# ppm-converter.net
KiCad netlist of a schematic drawn in EAGLE
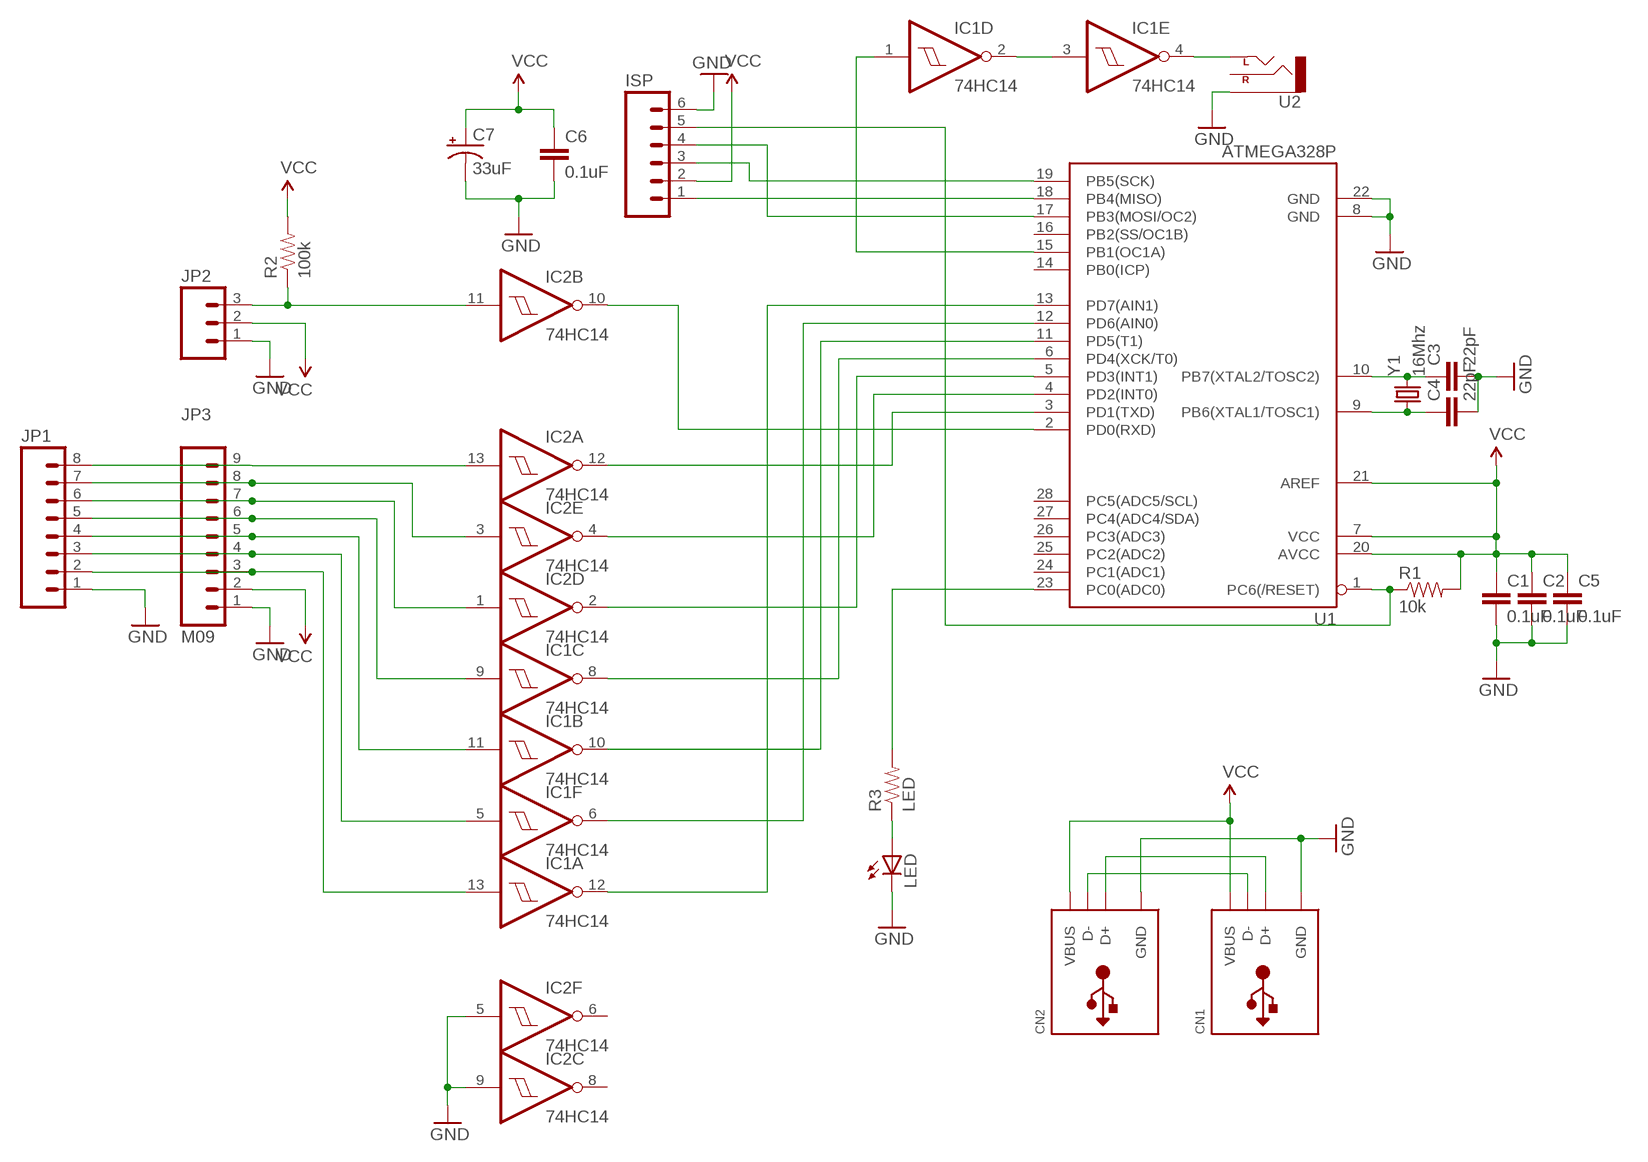
[diagram p0: schematic, sheet 1]

(export (version "E")
  (design (tool "Eeschema 10.0.6"))
  (components
    (comp (ref "C1")
      (value "0.1uF")
      (footprint "eagle-import:CAP-PTH-SMALL")
      (libsource (lib "eagle-import") (part "CAPPTH"))
    )
    (comp (ref "C2")
      (value "0.1uF")
      (footprint "eagle-import:CAP-PTH-SMALL")
      (libsource (lib "eagle-import") (part "CAPPTH"))
    )
    (comp (ref "C3")
      (value "22pF")
      (footprint "eagle-import:CAP-PTH-SMALL")
      (libsource (lib "eagle-import") (part "CAPPTH"))
    )
    (comp (ref "C4")
      (value "22pF")
      (footprint "eagle-import:CAP-PTH-SMALL")
      (libsource (lib "eagle-import") (part "CAPPTH"))
    )
    (comp (ref "C5")
      (value "0.1uF")
      (footprint "eagle-import:CAP-PTH-SMALL")
      (libsource (lib "eagle-import") (part "CAPPTH"))
    )
    (comp (ref "C6")
      (value "0.1uF")
      (footprint "eagle-import:CAP-PTH-SMALL")
      (libsource (lib "eagle-import") (part "CAPPTH"))
    )
    (comp (ref "C7")
      (value "33uF")
      (footprint "eagle-import:CPOL-RADIAL-100UF-25V")
      (libsource (lib "eagle-import") (part "CAP_POLPTH1"))
    )
    (comp (ref "CN1")
      (value "USB_TYPEAPTHFML")
      (footprint "eagle-import:USB_HOST-PTH")
      (libsource (lib "eagle-import") (part "USB_TYPEAPTHFML"))
    )
    (comp (ref "CN2")
      (value "USB_TYPEAPTHFML")
      (footprint "eagle-import:USB_HOST-PTH")
      (libsource (lib "eagle-import") (part "USB_TYPEAPTHFML"))
    )
    (comp (ref "IC1")
      (value "74HC14")
      (footprint "eagle-import:DIL14")
      (libsource (lib "eagle-import") (part "7414NHC"))
    )
    (comp (ref "IC2")
      (value "74HC14")
      (footprint "eagle-import:DIL14")
      (libsource (lib "eagle-import") (part "7414NHC"))
    )
    (comp (ref "ISP")
      (value "M06SIP")
      (footprint "eagle-import:1X06")
      (libsource (lib "eagle-import") (part "M06SIP"))
    )
    (comp (ref "JP1")
      (value "M081X08")
      (footprint "eagle-import:1X08")
      (libsource (lib "eagle-import") (part "M081X08"))
    )
    (comp (ref "JP2")
      (value "M03PTH")
      (footprint "eagle-import:1X03")
      (libsource (lib "eagle-import") (part "M03PTH"))
    )
    (comp (ref "JP3")
      (value "M09")
      (footprint "eagle-import:1X09")
      (libsource (lib "eagle-import") (part "M09"))
    )
    (comp (ref "LED")
      (value "LED5MM-KIT")
      (footprint "eagle-import:LED5MM-KIT")
      (libsource (lib "eagle-import") (part "LED5MM-KIT"))
    )
    (comp (ref "R1")
      (value "10k")
      (footprint "eagle-import:AXIAL-0.3")
      (libsource (lib "eagle-import") (part "RESISTORAXIAL-0.3"))
    )
    (comp (ref "R2")
      (value "100k")
      (footprint "eagle-import:AXIAL-0.3")
      (libsource (lib "eagle-import") (part "RESISTORAXIAL-0.3"))
    )
    (comp (ref "R3")
      (value "LED")
      (footprint "eagle-import:AXIAL-0.3")
      (libsource (lib "eagle-import") (part "RESISTORAXIAL-0.3"))
    )
    (comp (ref "U1")
      (value "ATMEGA328P")
      (footprint "eagle-import:DIL28-3")
      (libsource (lib "eagle-import") (part "ATMEGA328P_PDIP"))
    )
    (comp (ref "U2")
      (value "AUDIO-JACKPTH")
      (footprint "eagle-import:AUDIO-JACK")
      (libsource (lib "eagle-import") (part "AUDIO-JACKPTH"))
    )
    (comp (ref "Y1")
      (value "16Mhz")
      (footprint "eagle-import:HC49US")
      (libsource (lib "eagle-import") (part "CRYSTALHC49US"))
    )
  )
  (nets
    (net (code "1") (name "GND") (class "Default")
      (node (ref "C1") (pin "2") (pinfunction "2_2") (pintype "passive"))
      (node (ref "C2") (pin "2") (pinfunction "2_2") (pintype "passive"))
      (node (ref "C3") (pin "2") (pinfunction "2_2") (pintype "passive"))
      (node (ref "C4") (pin "2") (pinfunction "2_2") (pintype "passive"))
      (node (ref "C5") (pin "2") (pinfunction "2_2") (pintype "passive"))
      (node (ref "C6") (pin "2") (pinfunction "2_2") (pintype "passive"))
      (node (ref "C7") (pin "2") (pinfunction "-_2") (pintype "passive"))
      (node (ref "CN1") (pin "GND") (pinfunction "GND_GND") (pintype "power_in"))
      (node (ref "CN2") (pin "GND") (pinfunction "GND_GND") (pintype "power_in"))
      (node (ref "IC2") (pin "5") (pinfunction "I_5") (pintype "input"))
      (node (ref "IC2") (pin "9") (pinfunction "I_9") (pintype "input"))
      (node (ref "ISP") (pin "6") (pinfunction "6_6") (pintype "passive"))
      (node (ref "JP1") (pin "1") (pinfunction "1_1") (pintype "passive"))
      (node (ref "JP2") (pin "1") (pinfunction "1_1") (pintype "passive"))
      (node (ref "JP3") (pin "1") (pinfunction "1_1") (pintype "passive"))
      (node (ref "LED") (pin "K") (pinfunction "C_K") (pintype "passive"))
      (node (ref "U1") (pin "22") (pinfunction "GND_22") (pintype "bidirectional"))
      (node (ref "U1") (pin "8") (pinfunction "GND_8") (pintype "bidirectional"))
      (node (ref "U2") (pin "SLEEVE") (pinfunction "SLEEVE_SLEEVE") (pintype "bidirectional"))
    )
    (net (code "2") (name "Net-(CN1-PadD+)") (class "Default")
      (node (ref "CN1") (pin "D+") (pinfunction "D+_D+") (pintype "bidirectional"))
      (node (ref "CN2") (pin "D+") (pinfunction "D+_D+") (pintype "bidirectional"))
    )
    (net (code "3") (name "Net-(CN1-PadD-)") (class "Default")
      (node (ref "CN1") (pin "D-") (pinfunction "D-_D-") (pintype "bidirectional"))
      (node (ref "CN2") (pin "D-") (pinfunction "D-_D-") (pintype "bidirectional"))
    )
    (net (code "4") (name "Net-(IC1A-I)") (class "Default")
      (node (ref "IC1") (pin "13") (pinfunction "I_13") (pintype "input"))
      (node (ref "JP1") (pin "2") (pinfunction "2_2") (pintype "passive"))
      (node (ref "JP3") (pin "3") (pinfunction "3_3") (pintype "passive"))
    )
    (net (code "5") (name "Net-(IC1A-O)") (class "Default")
      (node (ref "IC1") (pin "12") (pinfunction "O_12") (pintype "output"))
      (node (ref "U1") (pin "13") (pinfunction "PD7(AIN1)_13") (pintype "bidirectional"))
    )
    (net (code "6") (name "Net-(IC1B-I)") (class "Default")
      (node (ref "IC1") (pin "11") (pinfunction "I_11") (pintype "input"))
      (node (ref "JP1") (pin "4") (pinfunction "4_4") (pintype "passive"))
      (node (ref "JP3") (pin "5") (pinfunction "5_5") (pintype "passive"))
    )
    (net (code "7") (name "Net-(IC1B-O)") (class "Default")
      (node (ref "IC1") (pin "10") (pinfunction "O_10") (pintype "output"))
      (node (ref "U1") (pin "11") (pinfunction "PD5(T1)_11") (pintype "bidirectional"))
    )
    (net (code "8") (name "Net-(IC1C-I)") (class "Default")
      (node (ref "IC1") (pin "9") (pinfunction "I_9") (pintype "input"))
      (node (ref "JP1") (pin "5") (pinfunction "5_5") (pintype "passive"))
      (node (ref "JP3") (pin "6") (pinfunction "6_6") (pintype "passive"))
    )
    (net (code "9") (name "Net-(IC1C-O)") (class "Default")
      (node (ref "IC1") (pin "8") (pinfunction "O_8") (pintype "output"))
      (node (ref "U1") (pin "6") (pinfunction "PD4(XCK/T0)_6") (pintype "bidirectional"))
    )
    (net (code "10") (name "Net-(IC1D-I)") (class "Default")
      (node (ref "IC1") (pin "1") (pinfunction "I_1") (pintype "input"))
      (node (ref "U1") (pin "15") (pinfunction "PB1(OC1A)_15") (pintype "bidirectional"))
    )
    (net (code "11") (name "Net-(IC1D-O)") (class "Default")
      (node (ref "IC1") (pin "2") (pinfunction "O_2") (pintype "output"))
      (node (ref "IC1") (pin "3") (pinfunction "I_3") (pintype "input"))
    )
    (net (code "12") (name "Net-(IC1E-O)") (class "Default")
      (node (ref "IC1") (pin "4") (pinfunction "O_4") (pintype "output"))
      (node (ref "U2") (pin "TIP") (pinfunction "LEFT_TIP") (pintype "bidirectional"))
    )
    (net (code "13") (name "Net-(IC1F-I)") (class "Default")
      (node (ref "IC1") (pin "5") (pinfunction "I_5") (pintype "input"))
      (node (ref "JP1") (pin "3") (pinfunction "3_3") (pintype "passive"))
      (node (ref "JP3") (pin "4") (pinfunction "4_4") (pintype "passive"))
    )
    (net (code "14") (name "Net-(IC1F-O)") (class "Default")
      (node (ref "IC1") (pin "6") (pinfunction "O_6") (pintype "output"))
      (node (ref "U1") (pin "12") (pinfunction "PD6(AIN0)_12") (pintype "bidirectional"))
    )
    (net (code "15") (name "Net-(IC2A-I)") (class "Default")
      (node (ref "IC2") (pin "13") (pinfunction "I_13") (pintype "input"))
      (node (ref "JP1") (pin "8") (pinfunction "8_8") (pintype "passive"))
      (node (ref "JP3") (pin "9") (pinfunction "9_9") (pintype "passive"))
    )
    (net (code "16") (name "Net-(IC2A-O)") (class "Default")
      (node (ref "IC2") (pin "12") (pinfunction "O_12") (pintype "output"))
      (node (ref "U1") (pin "3") (pinfunction "PD1(TXD)_3") (pintype "bidirectional"))
    )
    (net (code "17") (name "Net-(IC2B-I)") (class "Default")
      (node (ref "IC2") (pin "11") (pinfunction "I_11") (pintype "input"))
      (node (ref "JP2") (pin "3") (pinfunction "3_3") (pintype "passive"))
      (node (ref "R2") (pin "P$1") (pinfunction "1_P$1") (pintype "passive"))
    )
    (net (code "18") (name "Net-(IC2B-O)") (class "Default")
      (node (ref "IC2") (pin "10") (pinfunction "O_10") (pintype "output"))
      (node (ref "U1") (pin "2") (pinfunction "PD0(RXD)_2") (pintype "bidirectional"))
    )
    (net (code "19") (name "Net-(IC2D-I)") (class "Default")
      (node (ref "IC2") (pin "1") (pinfunction "I_1") (pintype "input"))
      (node (ref "JP1") (pin "6") (pinfunction "6_6") (pintype "passive"))
      (node (ref "JP3") (pin "7") (pinfunction "7_7") (pintype "passive"))
    )
    (net (code "20") (name "Net-(IC2D-O)") (class "Default")
      (node (ref "IC2") (pin "2") (pinfunction "O_2") (pintype "output"))
      (node (ref "U1") (pin "5") (pinfunction "PD3(INT1)_5") (pintype "bidirectional"))
    )
    (net (code "21") (name "Net-(IC2E-I)") (class "Default")
      (node (ref "IC2") (pin "3") (pinfunction "I_3") (pintype "input"))
      (node (ref "JP1") (pin "7") (pinfunction "7_7") (pintype "passive"))
      (node (ref "JP3") (pin "8") (pinfunction "8_8") (pintype "passive"))
    )
    (net (code "22") (name "Net-(IC2E-O)") (class "Default")
      (node (ref "IC2") (pin "4") (pinfunction "O_4") (pintype "output"))
      (node (ref "U1") (pin "4") (pinfunction "PD2(INT0)_4") (pintype "bidirectional"))
    )
    (net (code "23") (name "Net-(R1-1)") (class "Default")
      (node (ref "ISP") (pin "5") (pinfunction "5_5") (pintype "passive"))
      (node (ref "R1") (pin "P$1") (pinfunction "1_P$1") (pintype "passive"))
      (node (ref "U1") (pin "1") (pinfunction "PC6(/RESET)_1") (pintype "bidirectional"))
    )
    (net (code "24") (name "Net-(R3-1)") (class "Default")
      (node (ref "LED") (pin "A") (pinfunction "A_A") (pintype "passive"))
      (node (ref "R3") (pin "P$1") (pinfunction "1_P$1") (pintype "passive"))
    )
    (net (code "25") (name "Net-(R3-2)") (class "Default")
      (node (ref "R3") (pin "P$2") (pinfunction "2_P$2") (pintype "passive"))
      (node (ref "U1") (pin "23") (pinfunction "PC0(ADC0)_23") (pintype "bidirectional"))
    )
    (net (code "26") (name "Net-(U1-PB3(MOSI{slash}OC2))") (class "Default")
      (node (ref "ISP") (pin "4") (pinfunction "4_4") (pintype "passive"))
      (node (ref "U1") (pin "17") (pinfunction "PB3(MOSI/OC2)_17") (pintype "bidirectional"))
    )
    (net (code "27") (name "Net-(U1-PB4(MISO))") (class "Default")
      (node (ref "ISP") (pin "1") (pinfunction "1_1") (pintype "passive"))
      (node (ref "U1") (pin "18") (pinfunction "PB4(MISO)_18") (pintype "bidirectional"))
    )
    (net (code "28") (name "Net-(U1-PB5(SCK))") (class "Default")
      (node (ref "ISP") (pin "3") (pinfunction "3_3") (pintype "passive"))
      (node (ref "U1") (pin "19") (pinfunction "PB5(SCK)_19") (pintype "bidirectional"))
    )
    (net (code "29") (name "Net-(U1-PB6(XTAL1{slash}TOSC1))") (class "Default")
      (node (ref "C4") (pin "1") (pinfunction "1_1") (pintype "passive"))
      (node (ref "U1") (pin "9") (pinfunction "PB6(XTAL1/TOSC1)_9") (pintype "bidirectional"))
      (node (ref "Y1") (pin "1") (pinfunction "1_1") (pintype "passive"))
    )
    (net (code "30") (name "Net-(U1-PB7(XTAL2{slash}TOSC2))") (class "Default")
      (node (ref "C3") (pin "1") (pinfunction "1_1") (pintype "passive"))
      (node (ref "U1") (pin "10") (pinfunction "PB7(XTAL2/TOSC2)_10") (pintype "bidirectional"))
      (node (ref "Y1") (pin "2") (pinfunction "2_2") (pintype "passive"))
    )
    (net (code "31") (name "VCC") (class "Default")
      (node (ref "C1") (pin "1") (pinfunction "1_1") (pintype "passive"))
      (node (ref "C2") (pin "1") (pinfunction "1_1") (pintype "passive"))
      (node (ref "C5") (pin "1") (pinfunction "1_1") (pintype "passive"))
      (node (ref "C6") (pin "1") (pinfunction "1_1") (pintype "passive"))
      (node (ref "C7") (pin "1") (pinfunction "+_1") (pintype "passive"))
      (node (ref "CN1") (pin "VBUS") (pinfunction "VBUS_VBUS") (pintype "power_in"))
      (node (ref "CN2") (pin "VBUS") (pinfunction "VBUS_VBUS") (pintype "power_in"))
      (node (ref "ISP") (pin "2") (pinfunction "2_2") (pintype "passive"))
      (node (ref "JP2") (pin "2") (pinfunction "2_2") (pintype "passive"))
      (node (ref "JP3") (pin "2") (pinfunction "2_2") (pintype "passive"))
      (node (ref "R1") (pin "P$2") (pinfunction "2_P$2") (pintype "passive"))
      (node (ref "R2") (pin "P$2") (pinfunction "2_P$2") (pintype "passive"))
      (node (ref "U1") (pin "20") (pinfunction "AVCC_20") (pintype "bidirectional"))
      (node (ref "U1") (pin "21") (pinfunction "AREF_21") (pintype "bidirectional"))
      (node (ref "U1") (pin "7") (pinfunction "VCC_7") (pintype "bidirectional"))
    )
    (net (code "32") (name "unconnected-(IC2C-O-Pad8)") (class "Default")
      (node (ref "IC2") (pin "8") (pinfunction "O_8") (pintype "output"))
    )
    (net (code "33") (name "unconnected-(IC2F-O-Pad6)") (class "Default")
      (node (ref "IC2") (pin "6") (pinfunction "O_6") (pintype "output"))
    )
    (net (code "34") (name "unconnected-(U1-PB0(ICP)-Pad14)") (class "Default")
      (node (ref "U1") (pin "14") (pinfunction "PB0(ICP)_14") (pintype "bidirectional"))
    )
    (net (code "35") (name "unconnected-(U1-PB2(SS{slash}OC1B)-Pad16)") (class "Default")
      (node (ref "U1") (pin "16") (pinfunction "PB2(SS/OC1B)_16") (pintype "bidirectional"))
    )
    (net (code "36") (name "unconnected-(U1-PC1(ADC1)-Pad24)") (class "Default")
      (node (ref "U1") (pin "24") (pinfunction "PC1(ADC1)_24") (pintype "bidirectional"))
    )
    (net (code "37") (name "unconnected-(U1-PC2(ADC2)-Pad25)") (class "Default")
      (node (ref "U1") (pin "25") (pinfunction "PC2(ADC2)_25") (pintype "bidirectional"))
    )
    (net (code "38") (name "unconnected-(U1-PC3(ADC3)-Pad26)") (class "Default")
      (node (ref "U1") (pin "26") (pinfunction "PC3(ADC3)_26") (pintype "bidirectional"))
    )
    (net (code "39") (name "unconnected-(U1-PC4(ADC4{slash}SDA)-Pad27)") (class "Default")
      (node (ref "U1") (pin "27") (pinfunction "PC4(ADC4/SDA)_27") (pintype "bidirectional"))
    )
    (net (code "40") (name "unconnected-(U1-PC5(ADC5{slash}SCL)-Pad28)") (class "Default")
      (node (ref "U1") (pin "28") (pinfunction "PC5(ADC5/SCL)_28") (pintype "bidirectional"))
    )
    (net (code "41") (name "unconnected-(U2-RIGHT-PadRING)") (class "Default")
      (node (ref "U2") (pin "RING") (pinfunction "RIGHT_RING") (pintype "bidirectional"))
    )
  )
)
